# EncoderTBPCB.net
KiCad netlist of a schematic drawn in EAGLE
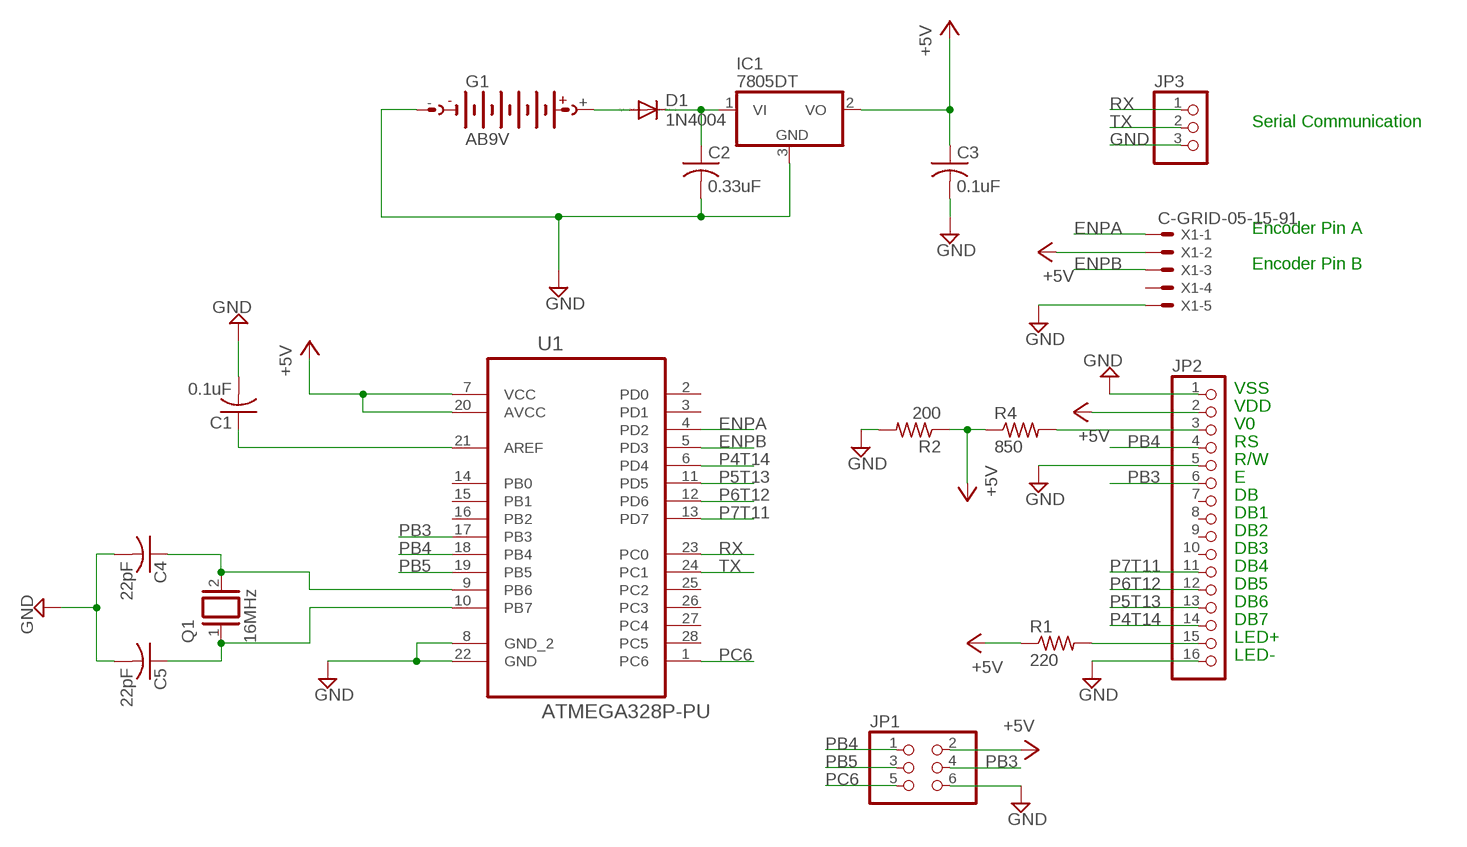
[diagram p0: schematic, sheet 1]

(export (version "E")
  (design (tool "Eeschema 10.0.6"))
  (components
    (comp (ref "C1")
      (value "0.1uF")
      (footprint "eagle-import:C0603")
      (libsource (lib "eagle-import") (part "C-USC0603"))
    )
    (comp (ref "C2")
      (value "0.33uF")
      (footprint "eagle-import:C0603")
      (libsource (lib "eagle-import") (part "C-USC0603"))
    )
    (comp (ref "C3")
      (value "0.1uF")
      (footprint "eagle-import:C0603")
      (libsource (lib "eagle-import") (part "C-USC0603"))
    )
    (comp (ref "C4")
      (value "22pF")
      (footprint "eagle-import:C0603")
      (libsource (lib "eagle-import") (part "C-USC0603"))
    )
    (comp (ref "C5")
      (value "22pF")
      (footprint "eagle-import:C0603")
      (libsource (lib "eagle-import") (part "C-USC0603"))
    )
    (comp (ref "D1")
      (value "1N4004")
      (footprint "eagle-import:DO41-10")
      (libsource (lib "eagle-import") (part "1N4004"))
    )
    (comp (ref "G1")
      (value "AB9V")
      (footprint "eagle-import:AB9V")
      (libsource (lib "eagle-import") (part "AB9V"))
    )
    (comp (ref "IC1")
      (value "7805DT")
      (footprint "eagle-import:TO252")
      (libsource (lib "eagle-import") (part "78DT05"))
    )
    (comp (ref "JP1")
      (value "PINHD-2X3")
      (footprint "eagle-import:2X03")
      (libsource (lib "eagle-import") (part "PINHD-2X3"))
    )
    (comp (ref "JP2")
      (value "PINHD-1X16")
      (footprint "eagle-import:1X16")
      (libsource (lib "eagle-import") (part "PINHD-1X16"))
    )
    (comp (ref "JP3")
      (value "PINHD-1X3")
      (footprint "eagle-import:1X03")
      (libsource (lib "eagle-import") (part "PINHD-1X3"))
    )
    (comp (ref "Q1")
      (value "16MHz")
      (footprint "eagle-import:QS")
      (libsource (lib "eagle-import") (part "XTAL/S"))
    )
    (comp (ref "R1")
      (value "220")
      (footprint "eagle-import:R0603")
      (libsource (lib "eagle-import") (part "R-US_R0603"))
    )
    (comp (ref "R2")
      (value "200")
      (footprint "eagle-import:R0603")
      (libsource (lib "eagle-import") (part "R-US_R0603"))
    )
    (comp (ref "R4")
      (value "850")
      (footprint "eagle-import:R0603")
      (libsource (lib "eagle-import") (part "R-US_R0603"))
    )
    (comp (ref "U1")
      (value "ATMEGA328P-PU")
      (footprint "eagle-import:DIP254P762X457-28")
      (libsource (lib "eagle-import") (part "ATMEGA328P-PU"))
    )
    (comp (ref "X1")
      (value "C-GRID-05-15-91")
      (footprint "eagle-import:15-91-05")
      (libsource (lib "eagle-import") (part "C-GRID-05-15-91"))
    )
  )
  (nets
    (net (code "1") (name "+5V") (class "Default")
      (node (ref "C3") (pin "1") (pinfunction "1_1") (pintype "passive"))
      (node (ref "IC1") (pin "2") (pinfunction "VO_2") (pintype "passive"))
      (node (ref "JP1") (pin "2") (pinfunction "2_2") (pintype "passive"))
      (node (ref "JP2") (pin "2") (pinfunction "2_2") (pintype "passive"))
      (node (ref "R1") (pin "1") (pinfunction "1_1") (pintype "passive"))
      (node (ref "R2") (pin "1") (pinfunction "1_1") (pintype "passive"))
      (node (ref "R4") (pin "1") (pinfunction "1_1") (pintype "passive"))
      (node (ref "U1") (pin "20") (pinfunction "AVCC_20") (pintype "power_in"))
      (node (ref "U1") (pin "7") (pinfunction "VCC_7") (pintype "power_in"))
      (node (ref "X1") (pin "2") (pinfunction "S_2") (pintype "passive"))
    )
    (net (code "2") (name "/ENPA") (class "Default")
      (node (ref "U1") (pin "4") (pinfunction "PD2_4") (pintype "bidirectional"))
      (node (ref "X1") (pin "1") (pinfunction "S_1") (pintype "passive"))
    )
    (net (code "3") (name "/ENPB") (class "Default")
      (node (ref "U1") (pin "5") (pinfunction "PD3_5") (pintype "bidirectional"))
      (node (ref "X1") (pin "3") (pinfunction "S_3") (pintype "passive"))
    )
    (net (code "4") (name "/P4T14") (class "Default")
      (node (ref "JP2") (pin "14") (pinfunction "14_14") (pintype "passive"))
      (node (ref "U1") (pin "6") (pinfunction "PD4_6") (pintype "bidirectional"))
    )
    (net (code "5") (name "/P5T13") (class "Default")
      (node (ref "JP2") (pin "13") (pinfunction "13_13") (pintype "passive"))
      (node (ref "U1") (pin "11") (pinfunction "PD5_11") (pintype "bidirectional"))
    )
    (net (code "6") (name "/P6T12") (class "Default")
      (node (ref "JP2") (pin "12") (pinfunction "12_12") (pintype "passive"))
      (node (ref "U1") (pin "12") (pinfunction "PD6_12") (pintype "bidirectional"))
    )
    (net (code "7") (name "/P7T11") (class "Default")
      (node (ref "JP2") (pin "11") (pinfunction "11_11") (pintype "passive"))
      (node (ref "U1") (pin "13") (pinfunction "PD7_13") (pintype "bidirectional"))
    )
    (net (code "8") (name "/PB3") (class "Default")
      (node (ref "JP1") (pin "4") (pinfunction "4_4") (pintype "passive"))
      (node (ref "JP2") (pin "6") (pinfunction "6_6") (pintype "passive"))
      (node (ref "U1") (pin "17") (pinfunction "PB3_17") (pintype "bidirectional"))
    )
    (net (code "9") (name "/PB4") (class "Default")
      (node (ref "JP1") (pin "1") (pinfunction "1_1") (pintype "passive"))
      (node (ref "JP2") (pin "4") (pinfunction "4_4") (pintype "passive"))
      (node (ref "U1") (pin "18") (pinfunction "PB4_18") (pintype "bidirectional"))
    )
    (net (code "10") (name "/PB5") (class "Default")
      (node (ref "JP1") (pin "3") (pinfunction "3_3") (pintype "passive"))
      (node (ref "U1") (pin "19") (pinfunction "PB5_19") (pintype "bidirectional"))
    )
    (net (code "11") (name "/PC6") (class "Default")
      (node (ref "JP1") (pin "5") (pinfunction "5_5") (pintype "passive"))
      (node (ref "U1") (pin "1") (pinfunction "PC6_1") (pintype "bidirectional"))
    )
    (net (code "12") (name "/RX") (class "Default")
      (node (ref "JP3") (pin "1") (pinfunction "1_1") (pintype "passive"))
      (node (ref "U1") (pin "23") (pinfunction "PC0_23") (pintype "bidirectional"))
    )
    (net (code "13") (name "/TX") (class "Default")
      (node (ref "JP3") (pin "2") (pinfunction "2_2") (pintype "passive"))
      (node (ref "U1") (pin "24") (pinfunction "PC1_24") (pintype "bidirectional"))
    )
    (net (code "14") (name "GND") (class "Default")
      (node (ref "C1") (pin "2") (pinfunction "2_2") (pintype "passive"))
      (node (ref "C2") (pin "2") (pinfunction "2_2") (pintype "passive"))
      (node (ref "C3") (pin "2") (pinfunction "2_2") (pintype "passive"))
      (node (ref "C4") (pin "2") (pinfunction "2_2") (pintype "passive"))
      (node (ref "C5") (pin "2") (pinfunction "2_2") (pintype "passive"))
      (node (ref "G1") (pin "-") (pinfunction "-_-") (pintype "passive"))
      (node (ref "IC1") (pin "3") (pinfunction "GND_3") (pintype "passive"))
      (node (ref "JP1") (pin "6") (pinfunction "6_6") (pintype "passive"))
      (node (ref "JP2") (pin "1") (pinfunction "1_1") (pintype "passive"))
      (node (ref "JP2") (pin "16") (pinfunction "16_16") (pintype "passive"))
      (node (ref "JP2") (pin "5") (pinfunction "5_5") (pintype "passive"))
      (node (ref "JP3") (pin "3") (pinfunction "3_3") (pintype "passive"))
      (node (ref "R2") (pin "2") (pinfunction "2_2") (pintype "passive"))
      (node (ref "U1") (pin "22") (pinfunction "GND_22") (pintype "passive"))
      (node (ref "U1") (pin "8") (pinfunction "GND_2_8") (pintype "passive"))
      (node (ref "X1") (pin "5") (pinfunction "S_5") (pintype "passive"))
    )
    (net (code "15") (name "Net-(D1-PadA)") (class "Default")
      (node (ref "D1") (pin "A") (pinfunction "A_A") (pintype "passive"))
      (node (ref "G1") (pin "+") (pinfunction "+_+") (pintype "passive"))
    )
    (net (code "16") (name "Net-(IC1-VI)") (class "Default")
      (node (ref "C2") (pin "1") (pinfunction "1_1") (pintype "passive"))
      (node (ref "D1") (pin "C") (pinfunction "C_C") (pintype "passive"))
      (node (ref "IC1") (pin "1") (pinfunction "VI_1") (pintype "input"))
    )
    (net (code "17") (name "Net-(JP2-Pad3)") (class "Default")
      (node (ref "JP2") (pin "3") (pinfunction "3_3") (pintype "passive"))
      (node (ref "R4") (pin "2") (pinfunction "2_2") (pintype "passive"))
    )
    (net (code "18") (name "Net-(JP2-Pad15)") (class "Default")
      (node (ref "JP2") (pin "15") (pinfunction "15_15") (pintype "passive"))
      (node (ref "R1") (pin "2") (pinfunction "2_2") (pintype "passive"))
    )
    (net (code "19") (name "Net-(U1-AREF)") (class "Default")
      (node (ref "C1") (pin "1") (pinfunction "1_1") (pintype "passive"))
      (node (ref "U1") (pin "21") (pinfunction "AREF_21") (pintype "input"))
    )
    (net (code "20") (name "Net-(U1-PB6)") (class "Default")
      (node (ref "C4") (pin "1") (pinfunction "1_1") (pintype "passive"))
      (node (ref "Q1") (pin "2") (pinfunction "2_2") (pintype "passive"))
      (node (ref "U1") (pin "9") (pinfunction "PB6_9") (pintype "bidirectional"))
    )
    (net (code "21") (name "Net-(U1-PB7)") (class "Default")
      (node (ref "C5") (pin "1") (pinfunction "1_1") (pintype "passive"))
      (node (ref "Q1") (pin "1") (pinfunction "1_1") (pintype "passive"))
      (node (ref "U1") (pin "10") (pinfunction "PB7_10") (pintype "bidirectional"))
    )
    (net (code "22") (name "unconnected-(JP2-Pad7)") (class "Default")
      (node (ref "JP2") (pin "7") (pinfunction "7_7") (pintype "passive"))
    )
    (net (code "23") (name "unconnected-(JP2-Pad8)") (class "Default")
      (node (ref "JP2") (pin "8") (pinfunction "8_8") (pintype "passive"))
    )
    (net (code "24") (name "unconnected-(JP2-Pad9)") (class "Default")
      (node (ref "JP2") (pin "9") (pinfunction "9_9") (pintype "passive"))
    )
    (net (code "25") (name "unconnected-(JP2-Pad10)") (class "Default")
      (node (ref "JP2") (pin "10") (pinfunction "10_10") (pintype "passive"))
    )
    (net (code "26") (name "unconnected-(U1-PB0-Pad14)") (class "Default")
      (node (ref "U1") (pin "14") (pinfunction "PB0_14") (pintype "bidirectional"))
    )
    (net (code "27") (name "unconnected-(U1-PB1-Pad15)") (class "Default")
      (node (ref "U1") (pin "15") (pinfunction "PB1_15") (pintype "bidirectional"))
    )
    (net (code "28") (name "unconnected-(U1-PB2-Pad16)") (class "Default")
      (node (ref "U1") (pin "16") (pinfunction "PB2_16") (pintype "bidirectional"))
    )
    (net (code "29") (name "unconnected-(U1-PC2-Pad25)") (class "Default")
      (node (ref "U1") (pin "25") (pinfunction "PC2_25") (pintype "bidirectional"))
    )
    (net (code "30") (name "unconnected-(U1-PC3-Pad26)") (class "Default")
      (node (ref "U1") (pin "26") (pinfunction "PC3_26") (pintype "bidirectional"))
    )
    (net (code "31") (name "unconnected-(U1-PC4-Pad27)") (class "Default")
      (node (ref "U1") (pin "27") (pinfunction "PC4_27") (pintype "bidirectional"))
    )
    (net (code "32") (name "unconnected-(U1-PC5-Pad28)") (class "Default")
      (node (ref "U1") (pin "28") (pinfunction "PC5_28") (pintype "bidirectional"))
    )
    (net (code "33") (name "unconnected-(U1-PD0-Pad2)") (class "Default")
      (node (ref "U1") (pin "2") (pinfunction "PD0_2") (pintype "bidirectional"))
    )
    (net (code "34") (name "unconnected-(U1-PD1-Pad3)") (class "Default")
      (node (ref "U1") (pin "3") (pinfunction "PD1_3") (pintype "bidirectional"))
    )
    (net (code "35") (name "unconnected-(X1D-S-Pad4)") (class "Default")
      (node (ref "X1") (pin "4") (pinfunction "S_4") (pintype "passive"))
    )
  )
)
